# Sheet2.net
KiCad netlist of a schematic drawn in Altium Designer
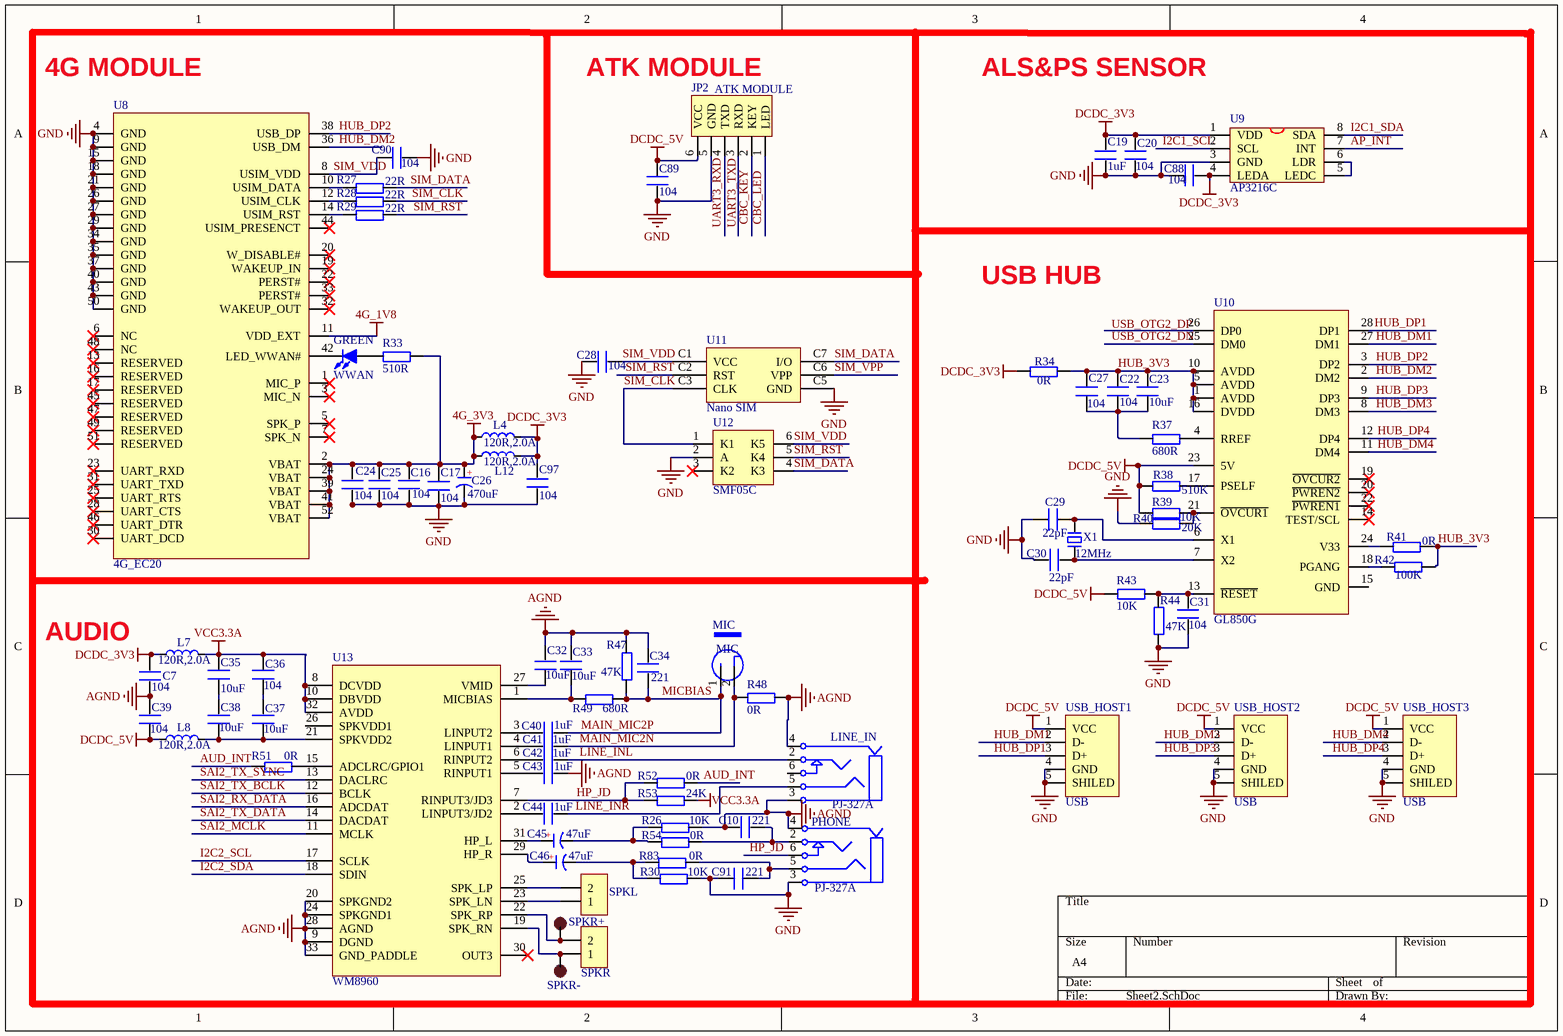
[diagram p0: Sheet2.SchDoc]

(export (version "E")
  (design (tool "Eeschema 10.0.6"))
  (components
    (comp (ref "C7") (value "104") (footprint "C 0603") (libsource (lib "linux_board_SCH") (part "C")))
    (comp (ref "C10") (value "221") (footprint "C 0603") (libsource (lib "linux_board_SCH") (part "C")))
    (comp (ref "C16") (value "104") (footprint "C 0603") (libsource (lib "linux_board_SCH") (part "C")))
    (comp (ref "C17") (value "104") (footprint "C 0603") (libsource (lib "linux_board_SCH") (part "C")))
    (comp (ref "C19") (value "1uF") (footprint "C 0603") (libsource (lib "linux_board_SCH") (part "C")))
    (comp (ref "C20") (value "104") (footprint "C 0603") (libsource (lib "linux_board_SCH") (part "C")))
    (comp (ref "C22") (value "104") (footprint "C 0603") (libsource (lib "linux_board_SCH") (part "C")))
    (comp (ref "C23") (value "10uF") (footprint "C 0603") (libsource (lib "linux_board_SCH") (part "C")))
    (comp (ref "C24") (value "104") (footprint "C 0603") (libsource (lib "linux_board_SCH") (part "C")))
    (comp (ref "C25") (value "104") (footprint "C 0603") (libsource (lib "linux_board_SCH") (part "C")))
    (comp (ref "C26")
      (value "470uF")
      (footprint "CM D(6.3*5.4)")
      (description "贴片电解电容")
      (fields (field (name "版权归属") "源创客"))
      (libsource (lib "linux_board_SCH") (part "C-CM"))
    )
    (comp (ref "C27") (value "104") (footprint "C 0603") (libsource (lib "linux_board_SCH") (part "C")))
    (comp (ref "C28") (value "104") (footprint "C 0603") (libsource (lib "linux_board_SCH") (part "C")))
    (comp (ref "C29") (value "22pF") (footprint "C 0603") (libsource (lib "linux_board_SCH") (part "C")))
    (comp (ref "C30") (value "22pF") (footprint "C 0603") (libsource (lib "linux_board_SCH") (part "C")))
    (comp (ref "C31") (value "104") (footprint "C 0603") (libsource (lib "linux_board_SCH") (part "C")))
    (comp (ref "C32") (value "10uF") (footprint "C 0603") (libsource (lib "linux_board_SCH") (part "C")))
    (comp (ref "C33") (value "10uF") (footprint "C 0603") (libsource (lib "linux_board_SCH") (part "C")))
    (comp (ref "C34") (value "221") (footprint "C 0603") (libsource (lib "linux_board_SCH") (part "C")))
    (comp (ref "C35") (value "10uF") (footprint "C 0603") (libsource (lib "linux_board_SCH") (part "C")))
    (comp (ref "C36") (value "104") (footprint "C 0603") (libsource (lib "linux_board_SCH") (part "C")))
    (comp (ref "C37") (value "10uF") (footprint "C 0603") (libsource (lib "linux_board_SCH") (part "C")))
    (comp (ref "C38") (value "10uF") (footprint "C 0603") (libsource (lib "linux_board_SCH") (part "C")))
    (comp (ref "C39") (value "104") (footprint "C 0603") (libsource (lib "linux_board_SCH") (part "C")))
    (comp (ref "C40") (value "1uF") (footprint "C 0603") (libsource (lib "linux_board_SCH") (part "C")))
    (comp (ref "C41") (value "1uF") (footprint "C 0603") (libsource (lib "linux_board_SCH") (part "C")))
    (comp (ref "C42") (value "1uF") (footprint "C 0603") (libsource (lib "linux_board_SCH") (part "C")))
    (comp (ref "C43") (value "1uF") (footprint "C 0603") (libsource (lib "linux_board_SCH") (part "C")))
    (comp (ref "C44") (value "1uF") (footprint "C 0603") (libsource (lib "linux_board_SCH") (part "C")))
    (comp (ref "C45")
      (value "47uF")
      (footprint "CM D(6.3*5.4)")
      (description "贴片电解电容")
      (fields (field (name "版权归属") "源创客"))
      (libsource (lib "") (part "C-CM_1"))
    )
    (comp (ref "C46")
      (value "47uF")
      (footprint "CM D(6.3*5.4)")
      (description "贴片电解电容")
      (fields (field (name "版权归属") "源创客"))
      (libsource (lib "") (part "C-CM_1"))
    )
    (comp (ref "C88") (value "104") (footprint "C 0603") (libsource (lib "linux_board_SCH") (part "C")))
    (comp (ref "C89") (value "104") (footprint "C 0603") (libsource (lib "linux_board_SCH") (part "C")))
    (comp (ref "C90") (value "104") (footprint "C 0603") (libsource (lib "linux_board_SCH") (part "C")))
    (comp (ref "C91") (value "221") (footprint "C 0603") (libsource (lib "linux_board_SCH") (part "C")))
    (comp (ref "C97") (value "104") (footprint "C 0603") (libsource (lib "linux_board_SCH") (part "C")))
    (comp (ref "GREEN")
      (value "WWAN")
      (footprint "LED 0805R")
      (description "贴片LED")
      (fields (field (name "版权归属") "源创客"))
      (libsource (lib "linux_board_SCH") (part "LED-SMD"))
    )
    (comp (ref "JP2")
      (value "ATK MODULE")
      (footprint "HEAD6")
      (description "ATK-HC05")
      (libsource (lib "linux_board_SCH") (part "ATK-HC05"))
    )
    (comp (ref "L4")
      (value "120R,2.0A")
      (footprint "L 0603")
      (description "小功率贴片电感磁珠")
      (fields (field (name "版权归属") "源创客"))
      (libsource (lib "linux_board_SCH") (part "L"))
    )
    (comp (ref "L7")
      (value "120R,2.0A")
      (footprint "L 0603")
      (description "小功率贴片电感磁珠")
      (fields (field (name "版权归属") "源创客"))
      (libsource (lib "linux_board_SCH") (part "L"))
    )
    (comp (ref "L8")
      (value "120R,2.0A")
      (footprint "L 0603")
      (description "小功率贴片电感磁珠")
      (fields (field (name "版权归属") "源创客"))
      (libsource (lib "linux_board_SCH") (part "L"))
    )
    (comp (ref "L12")
      (value "120R,2.0A")
      (footprint "L 0603")
      (description "小功率贴片电感磁珠")
      (fields (field (name "版权归属") "源创客"))
      (libsource (lib "linux_board_SCH") (part "L"))
    )
    (comp (ref "LINE_IN")
      (value "PJ-327A")
      (footprint "PJ327A")
      (libsource (lib "linux_board_SCH") (part "PJ-327A"))
    )
    (comp (ref "MIC") (value "MIC") (footprint "MIC-6022") (libsource (lib "linux_board_SCH") (part "MIC")))
    (comp (ref "PHONE")
      (value "PJ-327A")
      (footprint "PJ327A")
      (libsource (lib "linux_board_SCH") (part "PJ-327A"))
    )
    (comp (ref "R26") (value "10K") (footprint "R 0603") (libsource (lib "linux_board_SCH") (part "R")))
    (comp (ref "R27") (value "22R") (footprint "R 0603") (libsource (lib "linux_board_SCH") (part "R")))
    (comp (ref "R28") (value "22R") (footprint "R 0603") (libsource (lib "linux_board_SCH") (part "R")))
    (comp (ref "R29") (value "22R") (footprint "R 0603") (libsource (lib "linux_board_SCH") (part "R")))
    (comp (ref "R30") (value "10K") (footprint "R 0603") (libsource (lib "linux_board_SCH") (part "R")))
    (comp (ref "R33") (value "510R") (footprint "R 0603") (libsource (lib "linux_board_SCH") (part "R")))
    (comp (ref "R34") (value "0R") (footprint "R 0603") (libsource (lib "linux_board_SCH") (part "R")))
    (comp (ref "R37") (value "680R") (footprint "R 0603") (libsource (lib "linux_board_SCH") (part "R")))
    (comp (ref "R38") (value "510K") (footprint "R 0603") (libsource (lib "linux_board_SCH") (part "R")))
    (comp (ref "R39") (value "10K") (footprint "R 0603") (libsource (lib "linux_board_SCH") (part "R")))
    (comp (ref "R40") (value "20K") (footprint "R 0603") (libsource (lib "linux_board_SCH") (part "R")))
    (comp (ref "R41") (value "0R") (footprint "R 0603") (libsource (lib "linux_board_SCH") (part "R")))
    (comp (ref "R42") (value "100K") (footprint "R 0603") (libsource (lib "linux_board_SCH") (part "R")))
    (comp (ref "R43") (value "10K") (footprint "R 0603") (libsource (lib "linux_board_SCH") (part "R")))
    (comp (ref "R44") (value "47K") (footprint "R 0603") (libsource (lib "linux_board_SCH") (part "R")))
    (comp (ref "R47") (value "47K") (footprint "R 0603") (libsource (lib "linux_board_SCH") (part "R")))
    (comp (ref "R48") (value "0R") (footprint "R 0603") (libsource (lib "linux_board_SCH") (part "R")))
    (comp (ref "R49") (value "680R") (footprint "R 0603") (libsource (lib "linux_board_SCH") (part "R")))
    (comp (ref "R51") (value "0R") (footprint "R 0603") (libsource (lib "linux_board_SCH") (part "R")))
    (comp (ref "R52") (value "0R") (footprint "R 0603") (libsource (lib "linux_board_SCH") (part "R")))
    (comp (ref "R53") (value "24K") (footprint "R 0603") (libsource (lib "linux_board_SCH") (part "R")))
    (comp (ref "R54") (value "0R") (footprint "R 0603") (libsource (lib "linux_board_SCH") (part "R")))
    (comp (ref "R83") (value "0R") (footprint "R 0603") (libsource (lib "linux_board_SCH") (part "R")))
    (comp (ref "SPKL")
      (value "SPKL")
      (footprint "XH2.54-2P_H")
      (description "2P接插件")
      (fields (field (name "版权归属") "源创客"))
      (libsource (lib "linux_board_SCH") (part "Header 2"))
    )
    (comp (ref "SPKR")
      (value "SPKL")
      (footprint "XH2.54-2P_H")
      (description "2P接插件")
      (fields (field (name "版权归属") "源创客"))
      (libsource (lib "linux_board_SCH") (part "Header 2"))
    )
    (comp (ref "SPKR+")
      (value "SPK+")
      (footprint "TP-1.5")
      (description "测试点")
      (libsource (lib "linux_board_SCH") (part "TEST-POINT"))
    )
    (comp (ref "SPKR-")
      (value "SPK+")
      (footprint "TP-1.5")
      (description "测试点")
      (libsource (lib "linux_board_SCH") (part "TEST-POINT"))
    )
    (comp (ref "U8")
      (value "4G_EC20")
      (footprint "Mini PCIE 52P")
      (libsource (lib "linux_board_SCH") (part "4G-EC20"))
    )
    (comp (ref "U9")
      (value "AP3216C")
      (footprint "QFN8")
      (description "ALS+PS Sensor")
      (libsource (lib "linux_board_SCH") (part "AP3216C"))
    )
    (comp (ref "U10")
      (value "GL850G")
      (footprint "SSOP28_L")
      (libsource (lib "linux_board_SCH") (part "GL850G"))
    )
    (comp (ref "U11")
      (value "Nano SIM")
      (footprint "Nano SIM 7P")
      (libsource (lib "linux_board_SCH") (part "Nano SIM"))
    )
    (comp (ref "U12")
      (value "SMF05C")
      (footprint "SOT363-6L")
      (libsource (lib "linux_board_SCH") (part "SMF05C"))
    )
    (comp (ref "U13")
      (value "WM8960")
      (footprint "QFN32 5x5_L")
      (libsource (lib "linux_board_SCH") (part "WM8960"))
    )
    (comp (ref "USB_HOST1")
      (value "USB")
      (footprint "USB-A/S_E")
      (description "USB-A型母接口")
      (fields (field (name "版权归属") "源创客"))
      (libsource (lib "linux_board_SCH") (part "USB-A/S"))
    )
    (comp (ref "USB_HOST2")
      (value "USB")
      (footprint "USB-A/S_E")
      (description "USB-A型母接口")
      (fields (field (name "版权归属") "源创客"))
      (libsource (lib "linux_board_SCH") (part "USB-A/S"))
    )
    (comp (ref "USB_HOST3")
      (value "USB")
      (footprint "USB-A/S_E")
      (description "USB-A型母接口")
      (fields (field (name "版权归属") "源创客"))
      (libsource (lib "linux_board_SCH") (part "USB-A/S"))
    )
    (comp (ref "X1")
      (value "12MHz")
      (footprint "XTAL-49S DIP")
      (description "2脚无源晶振")
      (fields (field (name "版权归属") "源创客"))
      (libsource (lib "linux_board_SCH") (part "XTAL-2P"))
    )
  )
  (nets
    (net (code "1") (name "/AP_INT") (class "Default")
      (node (ref "U9") (pin "7") (pinfunction "INT_7") (pintype "passive"))
    )
    (net (code "2") (name "/AUD_INT") (class "Default")
      (node (ref "R51") (pin "1") (pintype "passive"))
      (node (ref "R52") (pin "2") (pintype "passive"))
    )
    (net (code "3") (name "/CBC_KEY") (class "Default")
      (node (ref "JP2") (pin "2") (pinfunction "KEY_2") (pintype "passive"))
    )
    (net (code "4") (name "/CBC_LED") (class "Default")
      (node (ref "JP2") (pin "1") (pinfunction "LED_1") (pintype "passive"))
    )
    (net (code "5") (name "/HP_JD") (class "Default")
      (node (ref "PHONE") (pin "6") (pinfunction "6_6") (pintype "passive"))
      (node (ref "R52") (pin "1") (pintype "passive"))
      (node (ref "R53") (pin "1") (pintype "passive"))
      (node (ref "U13") (pin "7") (pinfunction "RINPUT3/JD3_7") (pintype "passive"))
    )
    (net (code "6") (name "/HUB_3V3") (class "Default")
      (node (ref "C22") (pin "2") (pintype "passive"))
      (node (ref "C23") (pin "2") (pintype "passive"))
      (node (ref "C27") (pin "2") (pintype "passive"))
      (node (ref "R34") (pin "2") (pintype "passive"))
      (node (ref "R41") (pin "2") (pintype "passive"))
      (node (ref "R42") (pin "2") (pintype "passive"))
      (node (ref "U10") (pin "1") (pinfunction "AVDD_1") (pintype "passive"))
      (node (ref "U10") (pin "10") (pinfunction "AVDD_10") (pintype "passive"))
      (node (ref "U10") (pin "16") (pinfunction "DVDD_16") (pintype "passive"))
      (node (ref "U10") (pin "5") (pinfunction "AVDD_5") (pintype "passive"))
    )
    (net (code "7") (name "/HUB_DM1") (class "Default")
      (node (ref "U10") (pin "27") (pinfunction "DM1_27") (pintype "passive"))
      (node (ref "USB_HOST1") (pin "2") (pinfunction "D-_2") (pintype "passive"))
    )
    (net (code "8") (name "/HUB_DM2") (class "Default")
      (node (ref "U10") (pin "2") (pinfunction "DM2_2") (pintype "passive"))
      (node (ref "U8") (pin "36") (pinfunction "USB_DM_36") (pintype "passive"))
    )
    (net (code "9") (name "/HUB_DM3") (class "Default")
      (node (ref "U10") (pin "8") (pinfunction "DM3_8") (pintype "passive"))
      (node (ref "USB_HOST2") (pin "2") (pinfunction "D-_2") (pintype "passive"))
    )
    (net (code "10") (name "/HUB_DM4") (class "Default")
      (node (ref "U10") (pin "11") (pinfunction "DM4_11") (pintype "passive"))
      (node (ref "USB_HOST3") (pin "2") (pinfunction "D-_2") (pintype "passive"))
    )
    (net (code "11") (name "/HUB_DP1") (class "Default")
      (node (ref "U10") (pin "28") (pinfunction "DP1_28") (pintype "passive"))
      (node (ref "USB_HOST1") (pin "3") (pinfunction "D+_3") (pintype "passive"))
    )
    (net (code "12") (name "/HUB_DP2") (class "Default")
      (node (ref "U10") (pin "3") (pinfunction "DP2_3") (pintype "passive"))
      (node (ref "U8") (pin "38") (pinfunction "USB_DP_38") (pintype "passive"))
    )
    (net (code "13") (name "/HUB_DP3") (class "Default")
      (node (ref "U10") (pin "9") (pinfunction "DP3_9") (pintype "passive"))
      (node (ref "USB_HOST2") (pin "3") (pinfunction "D+_3") (pintype "passive"))
    )
    (net (code "14") (name "/HUB_DP4") (class "Default")
      (node (ref "U10") (pin "12") (pinfunction "DP4_12") (pintype "passive"))
      (node (ref "USB_HOST3") (pin "3") (pinfunction "D+_3") (pintype "passive"))
    )
    (net (code "15") (name "/I2C1_SCL") (class "Default")
      (node (ref "U9") (pin "2") (pinfunction "SCL_2") (pintype "passive"))
    )
    (net (code "16") (name "/I2C1_SDA") (class "Default")
      (node (ref "U9") (pin "8") (pinfunction "SDA_8") (pintype "passive"))
    )
    (net (code "17") (name "/I2C2_SCL") (class "Default")
      (node (ref "U13") (pin "17") (pinfunction "SCLK_17") (pintype "passive"))
    )
    (net (code "18") (name "/I2C2_SDA") (class "Default")
      (node (ref "U13") (pin "18") (pinfunction "SDIN_18") (pintype "passive"))
    )
    (net (code "19") (name "/LINE_INL") (class "Default")
      (node (ref "C42") (pin "2") (pintype "passive"))
      (node (ref "LINE_IN") (pin "2") (pinfunction "2_2") (pintype "passive"))
    )
    (net (code "20") (name "/LINE_INR") (class "Default")
      (node (ref "C44") (pin "2") (pintype "passive"))
      (node (ref "LINE_IN") (pin "5") (pinfunction "5_5") (pintype "passive"))
    )
    (net (code "21") (name "/MAIN_MIC2N") (class "Default")
      (node (ref "C41") (pin "2") (pintype "passive"))
      (node (ref "MIC") (pin "2") (pinfunction "GND_2") (pintype "passive"))
      (node (ref "R48") (pin "1") (pintype "passive"))
    )
    (net (code "22") (name "/MAIN_MIC2P") (class "Default")
      (node (ref "C34") (pin "1") (pintype "passive"))
      (node (ref "C40") (pin "2") (pintype "passive"))
      (node (ref "MIC") (pin "1") (pinfunction "VCC_1") (pintype "passive"))
      (node (ref "R47") (pin "1") (pintype "passive"))
      (node (ref "R49") (pin "2") (pintype "passive"))
    )
    (net (code "23") (name "/SAI2_MCLK") (class "Default")
      (node (ref "U13") (pin "11") (pinfunction "MCLK_11") (pintype "passive"))
    )
    (net (code "24") (name "/SAI2_RX_DATA") (class "Default")
      (node (ref "U13") (pin "16") (pinfunction "ADCDAT_16") (pintype "passive"))
    )
    (net (code "25") (name "/SAI2_TX_BCLK") (class "Default")
      (node (ref "U13") (pin "12") (pinfunction "BCLK_12") (pintype "passive"))
    )
    (net (code "26") (name "/SAI2_TX_DATA") (class "Default")
      (node (ref "U13") (pin "14") (pinfunction "DACDAT_14") (pintype "passive"))
    )
    (net (code "27") (name "/SAI2_TX_SYNC") (class "Default")
      (node (ref "U13") (pin "13") (pinfunction "DACLRC_13") (pintype "passive"))
    )
    (net (code "28") (name "/SIM_CLK") (class "Default")
      (node (ref "R28") (pin "2") (pintype "passive"))
      (node (ref "U11") (pin "C3") (pinfunction "CLK_C3") (pintype "passive"))
      (node (ref "U12") (pin "1") (pinfunction "K1_1") (pintype "passive"))
    )
    (net (code "29") (name "/SIM_DATA") (class "Default")
      (node (ref "R27") (pin "2") (pintype "passive"))
      (node (ref "U11") (pin "C7") (pinfunction "I/O_C7") (pintype "passive"))
      (node (ref "U12") (pin "4") (pinfunction "K3_4") (pintype "passive"))
    )
    (net (code "30") (name "/SIM_RST") (class "Default")
      (node (ref "R29") (pin "2") (pintype "passive"))
      (node (ref "U11") (pin "C2") (pinfunction "RST_C2") (pintype "passive"))
      (node (ref "U12") (pin "5") (pinfunction "K4_5") (pintype "passive"))
    )
    (net (code "31") (name "/SIM_VDD") (class "Default")
      (node (ref "C28") (pin "1") (pintype "passive"))
      (node (ref "C90") (pin "1") (pintype "passive"))
      (node (ref "U11") (pin "C1") (pinfunction "VCC_C1") (pintype "passive"))
      (node (ref "U12") (pin "6") (pinfunction "K5_6") (pintype "passive"))
      (node (ref "U8") (pin "8") (pinfunction "USIM_VDD_8") (pintype "passive"))
    )
    (net (code "32") (name "/SIM_VPP") (class "Default")
      (node (ref "U11") (pin "C6") (pinfunction "VPP_C6") (pintype "passive"))
    )
    (net (code "33") (name "/UART3_RXD") (class "Default")
      (node (ref "JP2") (pin "4") (pinfunction "TXD_4") (pintype "passive"))
    )
    (net (code "35") (name "/USB_OTG2_DN") (class "Default")
      (node (ref "U10") (pin "25") (pinfunction "DM0_25") (pintype "passive"))
    )
    (net (code "37") (name "4G_1V8") (class "Default")
      (node (ref "U8") (pin "11") (pinfunction "VDD_EXT_11") (pintype "passive"))
    )
    (net (code "38") (name "4G_3V3") (class "Default")
      (node (ref "C16") (pin "2") (pintype "passive"))
      (node (ref "C17") (pin "2") (pintype "passive"))
      (node (ref "C24") (pin "2") (pintype "passive"))
      (node (ref "C25") (pin "2") (pintype "passive"))
      (node (ref "C26") (pin "1") (pinfunction "A_1") (pintype "passive"))
      (node (ref "L12") (pin "1") (pinfunction "1_1") (pintype "passive"))
      (node (ref "L4") (pin "1") (pinfunction "1_1") (pintype "passive"))
      (node (ref "R33") (pin "2") (pintype "passive"))
      (node (ref "U8") (pin "2") (pinfunction "VBAT_2") (pintype "passive"))
      (node (ref "U8") (pin "24") (pinfunction "VBAT_24") (pintype "passive"))
      (node (ref "U8") (pin "39") (pinfunction "VBAT_39") (pintype "passive"))
      (node (ref "U8") (pin "41") (pinfunction "VBAT_41") (pintype "passive"))
      (node (ref "U8") (pin "52") (pinfunction "VBAT_52") (pintype "passive"))
    )
    (net (code "39") (name "AGND") (class "Default")
      (node (ref "C10") (pin "1") (pintype "passive"))
      (node (ref "C32") (pin "1") (pintype "passive"))
      (node (ref "C33") (pin "2") (pintype "passive"))
      (node (ref "C34") (pin "2") (pintype "passive"))
      (node (ref "C39") (pin "2") (pintype "passive"))
      (node (ref "C43") (pin "2") (pintype "passive"))
      (node (ref "C7") (pin "1") (pintype "passive"))
      (node (ref "LINE_IN") (pin "3") (pinfunction "1_3") (pintype "passive"))
      (node (ref "LINE_IN") (pin "4") (pinfunction "4_4") (pintype "passive"))
      (node (ref "PHONE") (pin "4") (pinfunction "4_4") (pintype "passive"))
      (node (ref "R26") (pin "2") (pintype "passive"))
      (node (ref "R47") (pin "2") (pintype "passive"))
      (node (ref "R48") (pin "2") (pintype "passive"))
      (node (ref "U13") (pin "20") (pinfunction "SPKGND2_20") (pintype "passive"))
      (node (ref "U13") (pin "24") (pinfunction "SPKGND1_24") (pintype "passive"))
      (node (ref "U13") (pin "28") (pinfunction "AGND_28") (pintype "passive"))
      (node (ref "U13") (pin "33") (pinfunction "GND_PADDLE_33") (pintype "passive"))
      (node (ref "U13") (pin "9") (pinfunction "DGND_9") (pintype "passive"))
    )
    (net (code "40") (name "DCDC_3V3") (class "Default")
      (node (ref "C19") (pin "2") (pintype "passive"))
      (node (ref "C20") (pin "2") (pintype "passive"))
      (node (ref "C7") (pin "2") (pintype "passive"))
      (node (ref "C88") (pin "1") (pintype "passive"))
      (node (ref "C97") (pin "2") (pintype "passive"))
      (node (ref "L12") (pin "2") (pinfunction "2_2") (pintype "passive"))
      (node (ref "L4") (pin "2") (pinfunction "2_2") (pintype "passive"))
      (node (ref "L7") (pin "1") (pinfunction "1_1") (pintype "passive"))
      (node (ref "R34") (pin "1") (pintype "passive"))
      (node (ref "U9") (pin "1") (pinfunction "VDD_1") (pintype "passive"))
      (node (ref "U9") (pin "4") (pinfunction "LEDA_4") (pintype "passive"))
    )
    (net (code "41") (name "DCDC_5V") (class "Default")
      (node (ref "C39") (pin "1") (pintype "passive"))
      (node (ref "C89") (pin "1") (pintype "passive"))
      (node (ref "JP2") (pin "6") (pinfunction "VCC_6") (pintype "passive"))
      (node (ref "L8") (pin "1") (pinfunction "1_1") (pintype "passive"))
      (node (ref "R38") (pin "1") (pintype "passive"))
      (node (ref "R39") (pin "1") (pintype "passive"))
      (node (ref "R43") (pin "1") (pintype "passive"))
      (node (ref "U10") (pin "23") (pinfunction "5V_23") (pintype "passive"))
      (node (ref "USB_HOST1") (pin "1") (pinfunction "VCC_1") (pintype "passive"))
      (node (ref "USB_HOST2") (pin "1") (pinfunction "VCC_1") (pintype "passive"))
      (node (ref "USB_HOST3") (pin "1") (pinfunction "VCC_1") (pintype "passive"))
    )
    (net (code "42") (name "GND") (class "Default")
      (node (ref "C16") (pin "1") (pintype "passive"))
      (node (ref "C17") (pin "1") (pintype "passive"))
      (node (ref "C19") (pin "1") (pintype "passive"))
      (node (ref "C20") (pin "1") (pintype "passive"))
      (node (ref "C24") (pin "1") (pintype "passive"))
      (node (ref "C25") (pin "1") (pintype "passive"))
      (node (ref "C26") (pin "2") (pinfunction "K_2") (pintype "passive"))
      (node (ref "C28") (pin "2") (pintype "passive"))
      (node (ref "C29") (pin "2") (pintype "passive"))
      (node (ref "C30") (pin "2") (pintype "passive"))
      (node (ref "C31") (pin "2") (pintype "passive"))
      (node (ref "C88") (pin "2") (pintype "passive"))
      (node (ref "C89") (pin "2") (pintype "passive"))
      (node (ref "C90") (pin "2") (pintype "passive"))
      (node (ref "C91") (pin "1") (pintype "passive"))
      (node (ref "C97") (pin "1") (pintype "passive"))
      (node (ref "JP2") (pin "5") (pinfunction "GND_5") (pintype "passive"))
      (node (ref "PHONE") (pin "3") (pinfunction "1_3") (pintype "passive"))
      (node (ref "R30") (pin "2") (pintype "passive"))
      (node (ref "R40") (pin "1") (pintype "passive"))
      (node (ref "R44") (pin "1") (pintype "passive"))
      (node (ref "U11") (pin "C5") (pinfunction "GND_C5") (pintype "passive"))
      (node (ref "U12") (pin "2") (pinfunction "A_2") (pintype "passive"))
      (node (ref "U8") (pin "15") (pinfunction "GND_15") (pintype "passive"))
      (node (ref "U8") (pin "18") (pinfunction "GND_18") (pintype "passive"))
      (node (ref "U8") (pin "21") (pinfunction "GND_21") (pintype "passive"))
      (node (ref "U8") (pin "26") (pinfunction "GND_26") (pintype "passive"))
      (node (ref "U8") (pin "27") (pinfunction "GND_27") (pintype "passive"))
      (node (ref "U8") (pin "29") (pinfunction "GND_29") (pintype "passive"))
      (node (ref "U8") (pin "34") (pinfunction "GND_34") (pintype "passive"))
      (node (ref "U8") (pin "35") (pinfunction "GND_35") (pintype "passive"))
      (node (ref "U8") (pin "37") (pinfunction "GND_37") (pintype "passive"))
      (node (ref "U8") (pin "4") (pinfunction "GND_4") (pintype "passive"))
      (node (ref "U8") (pin "40") (pinfunction "GND_40") (pintype "passive"))
      (node (ref "U8") (pin "43") (pinfunction "GND_43") (pintype "passive"))
      (node (ref "U8") (pin "50") (pinfunction "GND_50") (pintype "passive"))
      (node (ref "U8") (pin "9") (pinfunction "GND_9") (pintype "passive"))
      (node (ref "U9") (pin "3") (pinfunction "GND_3") (pintype "passive"))
      (node (ref "USB_HOST1") (pin "4") (pinfunction "GND_4") (pintype "passive"))
      (node (ref "USB_HOST1") (pin "5") (pinfunction "SHILED_5") (pintype "passive"))
      (node (ref "USB_HOST2") (pin "4") (pinfunction "GND_4") (pintype "passive"))
      (node (ref "USB_HOST2") (pin "5") (pinfunction "SHILED_5") (pintype "passive"))
      (node (ref "USB_HOST3") (pin "4") (pinfunction "GND_4") (pintype "passive"))
      (node (ref "USB_HOST3") (pin "5") (pinfunction "SHILED_5") (pintype "passive"))
    )
    (net (code "43") (name "Net-(C10-Pad2)") (class "Default")
      (node (ref "C10") (pin "2") (pintype "passive"))
      (node (ref "PHONE") (pin "2") (pinfunction "2_2") (pintype "passive"))
      (node (ref "R54") (pin "2") (pintype "passive"))
    )
    (net (code "44") (name "Net-(C22-Pad1)") (class "Default")
      (node (ref "C22") (pin "1") (pintype "passive"))
      (node (ref "C23") (pin "1") (pintype "passive"))
      (node (ref "C27") (pin "1") (pintype "passive"))
      (node (ref "R37") (pin "1") (pintype "passive"))
    )
    (net (code "45") (name "Net-(C35-Pad1)") (class "Default")
      (node (ref "C35") (pin "1") (pintype "passive"))
      (node (ref "C38") (pin "2") (pintype "passive"))
    )
    (net (code "46") (name "Net-(C36-Pad1)") (class "Default")
      (node (ref "C36") (pin "1") (pintype "passive"))
      (node (ref "C37") (pin "2") (pintype "passive"))
    )
    (net (code "47") (name "Net-(C45-A)") (class "Default")
      (node (ref "C45") (pin "1") (pinfunction "A_1") (pintype "passive"))
      (node (ref "U13") (pin "31") (pinfunction "HP_L_31") (pintype "passive"))
    )
    (net (code "48") (name "Net-(C45-K)") (class "Default")
      (node (ref "C45") (pin "2") (pinfunction "K_2") (pintype "passive"))
      (node (ref "R26") (pin "1") (pintype "passive"))
      (node (ref "R54") (pin "1") (pintype "passive"))
    )
    (net (code "49") (name "Net-(C46-A)") (class "Default")
      (node (ref "C46") (pin "1") (pinfunction "A_1") (pintype "passive"))
      (node (ref "U13") (pin "29") (pinfunction "HP_R_29") (pintype "passive"))
    )
    (net (code "50") (name "Net-(C46-K)") (class "Default")
      (node (ref "C46") (pin "2") (pinfunction "K_2") (pintype "passive"))
      (node (ref "R30") (pin "1") (pintype "passive"))
      (node (ref "R83") (pin "1") (pintype "passive"))
    )
    (net (code "51") (name "Net-(C91-Pad2)") (class "Default")
      (node (ref "C91") (pin "2") (pintype "passive"))
      (node (ref "PHONE") (pin "5") (pinfunction "5_5") (pintype "passive"))
      (node (ref "R83") (pin "2") (pintype "passive"))
    )
    (net (code "52") (name "Net-(GREEN-A)") (class "Default")
      (node (ref "GREEN") (pin "1") (pinfunction "A_1") (pintype "passive"))
      (node (ref "R33") (pin "1") (pintype "passive"))
    )
    (net (code "53") (name "Net-(GREEN-K)") (class "Default")
      (node (ref "GREEN") (pin "2") (pinfunction "K_2") (pintype "passive"))
      (node (ref "U8") (pin "42") (pinfunction "LED_WWAN#_42") (pintype "passive"))
    )
    (net (code "54") (name "Net-(U8-USIM_CLK)") (class "Default")
      (node (ref "R28") (pin "1") (pintype "passive"))
      (node (ref "U8") (pin "12") (pinfunction "USIM_CLK_12") (pintype "passive"))
    )
    (net (code "55") (name "Net-(U8-USIM_DATA)") (class "Default")
      (node (ref "R27") (pin "1") (pintype "passive"))
      (node (ref "U8") (pin "10") (pinfunction "USIM_DATA_10") (pintype "passive"))
    )
    (net (code "56") (name "Net-(U8-USIM_RST)") (class "Default")
      (node (ref "R29") (pin "1") (pintype "passive"))
      (node (ref "U8") (pin "14") (pinfunction "USIM_RST_14") (pintype "passive"))
    )
    (net (code "57") (name "Net-(U9-LDR)") (class "Default")
      (node (ref "U9") (pin "5") (pinfunction "LEDC_5") (pintype "passive"))
      (node (ref "U9") (pin "6") (pinfunction "LDR_6") (pintype "passive"))
    )
    (net (code "58") (name "Net-(U10-PGANG)") (class "Default")
      (node (ref "R42") (pin "1") (pintype "passive"))
      (node (ref "U10") (pin "18") (pinfunction "PGANG_18") (pintype "passive"))
    )
    (net (code "59") (name "Net-(U10-PSELF)") (class "Default")
      (node (ref "R38") (pin "2") (pintype "passive"))
      (node (ref "U10") (pin "17") (pinfunction "PSELF_17") (pintype "passive"))
    )
    (net (code "60") (name "Net-(U10-RREF)") (class "Default")
      (node (ref "R37") (pin "2") (pintype "passive"))
      (node (ref "U10") (pin "4") (pinfunction "RREF_4") (pintype "passive"))
    )
    (net (code "61") (name "Net-(U10-V33)") (class "Default")
      (node (ref "R41") (pin "1") (pintype "passive"))
      (node (ref "U10") (pin "24") (pinfunction "V33_24") (pintype "passive"))
    )
    (net (code "62") (name "Net-(U10-X1)") (class "Default")
      (node (ref "C29") (pin "1") (pintype "passive"))
      (node (ref "U10") (pin "6") (pinfunction "X1_6") (pintype "passive"))
      (node (ref "X1") (pin "2") (pinfunction "2_2") (pintype "passive"))
    )
    (net (code "63") (name "Net-(U10-X2)") (class "Default")
      (node (ref "C30") (pin "1") (pintype "passive"))
      (node (ref "U10") (pin "7") (pinfunction "X2_7") (pintype "passive"))
      (node (ref "X1") (pin "1") (pinfunction "1_1") (pintype "passive"))
    )
    (net (code "64") (name "Net-(U10-~{OVCUR1})") (class "Default")
      (node (ref "R39") (pin "2") (pintype "passive"))
      (node (ref "R40") (pin "2") (pintype "passive"))
      (node (ref "U10") (pin "21") (pinfunction "~{OVCUR1}_21") (pintype "passive"))
    )
    (net (code "65") (name "Net-(U10-~{RESET})") (class "Default")
      (node (ref "C31") (pin "1") (pintype "passive"))
      (node (ref "R43") (pin "2") (pintype "passive"))
      (node (ref "R44") (pin "2") (pintype "passive"))
      (node (ref "U10") (pin "13") (pinfunction "~{RESET}_13") (pintype "passive"))
    )
    (net (code "66") (name "Net-(U13-ADCLRC{slash}GPIO1)") (class "Default")
      (node (ref "R51") (pin "2") (pintype "passive"))
      (node (ref "U13") (pin "15") (pinfunction "ADCLRC/GPIO1_15") (pintype "passive"))
    )
    (net (code "67") (name "Net-(U13-LINPUT1)") (class "Default")
      (node (ref "C41") (pin "1") (pintype "passive"))
      (node (ref "U13") (pin "4") (pinfunction "LINPUT1_4") (pintype "passive"))
    )
    (net (code "68") (name "Net-(U13-LINPUT2)") (class "Default")
      (node (ref "C40") (pin "1") (pintype "passive"))
      (node (ref "U13") (pin "3") (pinfunction "LINPUT2_3") (pintype "passive"))
    )
    (net (code "69") (name "Net-(U13-LINPUT3{slash}JD2)") (class "Default")
      (node (ref "C44") (pin "1") (pintype "passive"))
      (node (ref "U13") (pin "2") (pinfunction "LINPUT3/JD2_2") (pintype "passive"))
    )
    (net (code "70") (name "Net-(U13-MICBIAS)") (class "Default")
      (node (ref "C33") (pin "1") (pintype "passive"))
      (node (ref "R49") (pin "1") (pintype "passive"))
      (node (ref "U13") (pin "1") (pinfunction "MICBIAS_1") (pintype "passive"))
    )
    (net (code "71") (name "Net-(U13-RINPUT1)") (class "Default")
      (node (ref "C43") (pin "1") (pintype "passive"))
      (node (ref "U13") (pin "5") (pinfunction "RINPUT1_5") (pintype "passive"))
    )
    (net (code "72") (name "Net-(U13-RINPUT2)") (class "Default")
      (node (ref "C42") (pin "1") (pintype "passive"))
      (node (ref "U13") (pin "6") (pinfunction "RINPUT2_6") (pintype "passive"))
    )
    (net (code "73") (name "Net-(U13-SPKVDD2)") (class "Default")
      (node (ref "C37") (pin "1") (pintype "passive"))
      (node (ref "C38") (pin "1") (pintype "passive"))
      (node (ref "L8") (pin "2") (pinfunction "2_2") (pintype "passive"))
      (node (ref "U13") (pin "21") (pinfunction "SPKVDD2_21") (pintype "passive"))
    )
    (net (code "74") (name "Net-(U13-SPK_LN)") (class "Default")
      (node (ref "SPKL") (pin "1") (pinfunction "1_1") (pintype "passive"))
      (node (ref "U13") (pin "23") (pinfunction "SPK_LN_23") (pintype "passive"))
    )
    (net (code "75") (name "Net-(U13-SPK_LP)") (class "Default")
      (node (ref "SPKL") (pin "2") (pinfunction "2_2") (pintype "passive"))
      (node (ref "U13") (pin "25") (pinfunction "SPK_LP_25") (pintype "passive"))
    )
    (net (code "76") (name "Net-(U13-SPK_RN)") (class "Default")
      (node (ref "SPKR") (pin "1") (pinfunction "1_1") (pintype "passive"))
      (node (ref "SPKR-") (pin "1") (pinfunction "1_1") (pintype "passive"))
      (node (ref "U13") (pin "19") (pinfunction "SPK_RN_19") (pintype "passive"))
    )
    (net (code "77") (name "Net-(U13-SPK_RP)") (class "Default")
      (node (ref "SPKR") (pin "2") (pinfunction "2_2") (pintype "passive"))
      (node (ref "SPKR+") (pin "1") (pinfunction "1_1") (pintype "passive"))
      (node (ref "U13") (pin "22") (pinfunction "SPK_RP_22") (pintype "passive"))
    )
    (net (code "78") (name "Net-(U13-VMID)") (class "Default")
      (node (ref "C32") (pin "2") (pintype "passive"))
      (node (ref "U13") (pin "27") (pinfunction "VMID_27") (pintype "passive"))
    )
    (net (code "79") (name "VCC3.3A") (class "Default")
      (node (ref "C35") (pin "2") (pintype "passive"))
      (node (ref "C36") (pin "2") (pintype "passive"))
      (node (ref "L7") (pin "2") (pinfunction "2_2") (pintype "passive"))
      (node (ref "R53") (pin "2") (pintype "passive"))
      (node (ref "U13") (pin "10") (pinfunction "DBVDD_10") (pintype "passive"))
      (node (ref "U13") (pin "32") (pinfunction "AVDD_32") (pintype "passive"))
      (node (ref "U13") (pin "8") (pinfunction "DCVDD_8") (pintype "passive"))
    )
    (net (code "80") (name "unconnected-(JP2-RXD-Pad3)") (class "Default")
      (node (ref "JP2") (pin "3") (pinfunction "RXD_3") (pintype "passive"))
    )
    (net (code "81") (name "unconnected-(LINE_IN-Pad6)") (class "Default")
      (node (ref "LINE_IN") (pin "6") (pinfunction "6_6") (pintype "passive"))
    )
    (net (code "82") (name "unconnected-(U8-MIC_N-Pad3)") (class "Default")
      (node (ref "U8") (pin "3") (pinfunction "MIC_N_3") (pintype "passive+no_connect"))
    )
    (net (code "83") (name "unconnected-(U8-MIC_P-Pad1)") (class "Default")
      (node (ref "U8") (pin "1") (pinfunction "MIC_P_1") (pintype "passive+no_connect"))
    )
    (net (code "84") (name "unconnected-(U8-NC-Pad6)") (class "Default")
      (node (ref "U8") (pin "6") (pinfunction "NC_6") (pintype "passive+no_connect"))
    )
    (net (code "85") (name "unconnected-(U8-NC-Pad48)") (class "Default")
      (node (ref "U8") (pin "48") (pinfunction "NC_48") (pintype "passive+no_connect"))
    )
    (net (code "86") (name "unconnected-(U8-PERST#-Pad22)") (class "Default")
      (node (ref "U8") (pin "22") (pinfunction "PERST#_22") (pintype "passive+no_connect"))
    )
    (net (code "87") (name "unconnected-(U8-PERST#-Pad33)") (class "Default")
      (node (ref "U8") (pin "33") (pinfunction "PERST#_33") (pintype "passive+no_connect"))
    )
    (net (code "88") (name "unconnected-(U8-RESERVED-Pad13)") (class "Default")
      (node (ref "U8") (pin "13") (pinfunction "RESERVED_13") (pintype "passive+no_connect"))
    )
    (net (code "89") (name "unconnected-(U8-RESERVED-Pad16)") (class "Default")
      (node (ref "U8") (pin "16") (pinfunction "RESERVED_16") (pintype "passive+no_connect"))
    )
    (net (code "90") (name "unconnected-(U8-RESERVED-Pad17)") (class "Default")
      (node (ref "U8") (pin "17") (pinfunction "RESERVED_17") (pintype "passive+no_connect"))
    )
    (net (code "91") (name "unconnected-(U8-RESERVED-Pad45)") (class "Default")
      (node (ref "U8") (pin "45") (pinfunction "RESERVED_45") (pintype "passive+no_connect"))
    )
    (net (code "92") (name "unconnected-(U8-RESERVED-Pad47)") (class "Default")
      (node (ref "U8") (pin "47") (pinfunction "RESERVED_47") (pintype "passive+no_connect"))
    )
    (net (code "93") (name "unconnected-(U8-RESERVED-Pad49)") (class "Default")
      (node (ref "U8") (pin "49") (pinfunction "RESERVED_49") (pintype "passive+no_connect"))
    )
    (net (code "94") (name "unconnected-(U8-RESERVED-Pad51)") (class "Default")
      (node (ref "U8") (pin "51") (pinfunction "RESERVED_51") (pintype "passive+no_connect"))
    )
    (net (code "95") (name "unconnected-(U8-SPK_N-Pad7)") (class "Default")
      (node (ref "U8") (pin "7") (pinfunction "SPK_N_7") (pintype "passive+no_connect"))
    )
    (net (code "96") (name "unconnected-(U8-SPK_P-Pad5)") (class "Default")
      (node (ref "U8") (pin "5") (pinfunction "SPK_P_5") (pintype "passive+no_connect"))
    )
    (net (code "97") (name "unconnected-(U8-UART_CTS-Pad28)") (class "Default")
      (node (ref "U8") (pin "28") (pinfunction "UART_CTS_28") (pintype "passive+no_connect"))
    )
    (net (code "98") (name "unconnected-(U8-UART_DCD-Pad30)") (class "Default")
      (node (ref "U8") (pin "30") (pinfunction "UART_DCD_30") (pintype "passive+no_connect"))
    )
    (net (code "99") (name "unconnected-(U8-UART_DTR-Pad46)") (class "Default")
      (node (ref "U8") (pin "46") (pinfunction "UART_DTR_46") (pintype "passive+no_connect"))
    )
    (net (code "100") (name "unconnected-(U8-UART_RTS-Pad25)") (class "Default")
      (node (ref "U8") (pin "25") (pinfunction "UART_RTS_25") (pintype "passive+no_connect"))
    )
    (net (code "101") (name "unconnected-(U8-UART_RXD-Pad23)") (class "Default")
      (node (ref "U8") (pin "23") (pinfunction "UART_RXD_23") (pintype "passive+no_connect"))
    )
    (net (code "102") (name "unconnected-(U8-UART_TXD-Pad31)") (class "Default")
      (node (ref "U8") (pin "31") (pinfunction "UART_TXD_31") (pintype "passive+no_connect"))
    )
    (net (code "103") (name "unconnected-(U8-USIM_PRESENCT-Pad44)") (class "Default")
      (node (ref "U8") (pin "44") (pinfunction "USIM_PRESENCT_44") (pintype "passive+no_connect"))
    )
    (net (code "104") (name "unconnected-(U8-WAKEUP_IN-Pad19)") (class "Default")
      (node (ref "U8") (pin "19") (pinfunction "WAKEUP_IN_19") (pintype "passive+no_connect"))
    )
    (net (code "105") (name "unconnected-(U8-WAKEUP_OUT-Pad32)") (class "Default")
      (node (ref "U8") (pin "32") (pinfunction "WAKEUP_OUT_32") (pintype "passive+no_connect"))
    )
    (net (code "106") (name "unconnected-(U8-W_DISABLE#-Pad20)") (class "Default")
      (node (ref "U8") (pin "20") (pinfunction "W_DISABLE#_20") (pintype "passive+no_connect"))
    )
    (net (code "107") (name "unconnected-(U10-DP0-Pad26)") (class "Default")
      (node (ref "U10") (pin "26") (pinfunction "DP0_26") (pintype "passive"))
    )
    (net (code "108") (name "unconnected-(U10-GND-Pad15)") (class "Default")
      (node (ref "U10") (pin "15") (pinfunction "GND_15") (pintype "passive"))
    )
    (net (code "109") (name "unconnected-(U10-TEST{slash}SCL-Pad14)") (class "Default")
      (node (ref "U10") (pin "14") (pinfunction "TEST/SCL_14") (pintype "passive+no_connect"))
    )
    (net (code "110") (name "unconnected-(U10-~{OVCUR2}-Pad19)") (class "Default")
      (node (ref "U10") (pin "19") (pinfunction "~{OVCUR2}_19") (pintype "passive+no_connect"))
    )
    (net (code "111") (name "unconnected-(U10-~{PWREN1}-Pad22)") (class "Default")
      (node (ref "U10") (pin "22") (pinfunction "~{PWREN1}_22") (pintype "passive+no_connect"))
    )
    (net (code "112") (name "unconnected-(U10-~{PWREN2}-Pad20)") (class "Default")
      (node (ref "U10") (pin "20") (pinfunction "~{PWREN2}_20") (pintype "passive+no_connect"))
    )
    (net (code "113") (name "unconnected-(U11-NC-PadC4)") (class "Default")
      (node (ref "U11") (pin "C4") (pinfunction "NC_C4") (pintype "passive"))
    )
    (net (code "114") (name "unconnected-(U12-K2-Pad3)") (class "Default")
      (node (ref "U12") (pin "3") (pinfunction "K2_3") (pintype "passive+no_connect"))
    )
    (net (code "115") (name "unconnected-(U13-OUT3-Pad30)") (class "Default")
      (node (ref "U13") (pin "30") (pinfunction "OUT3_30") (pintype "passive+no_connect"))
    )
    (net (code "116") (name "unconnected-(U13-SPKVDD1-Pad26)") (class "Default")
      (node (ref "U13") (pin "26") (pinfunction "SPKVDD1_26") (pintype "passive"))
    )
  )
)
